# som.net
KiCad netlist of a schematic drawn in Altium Designer
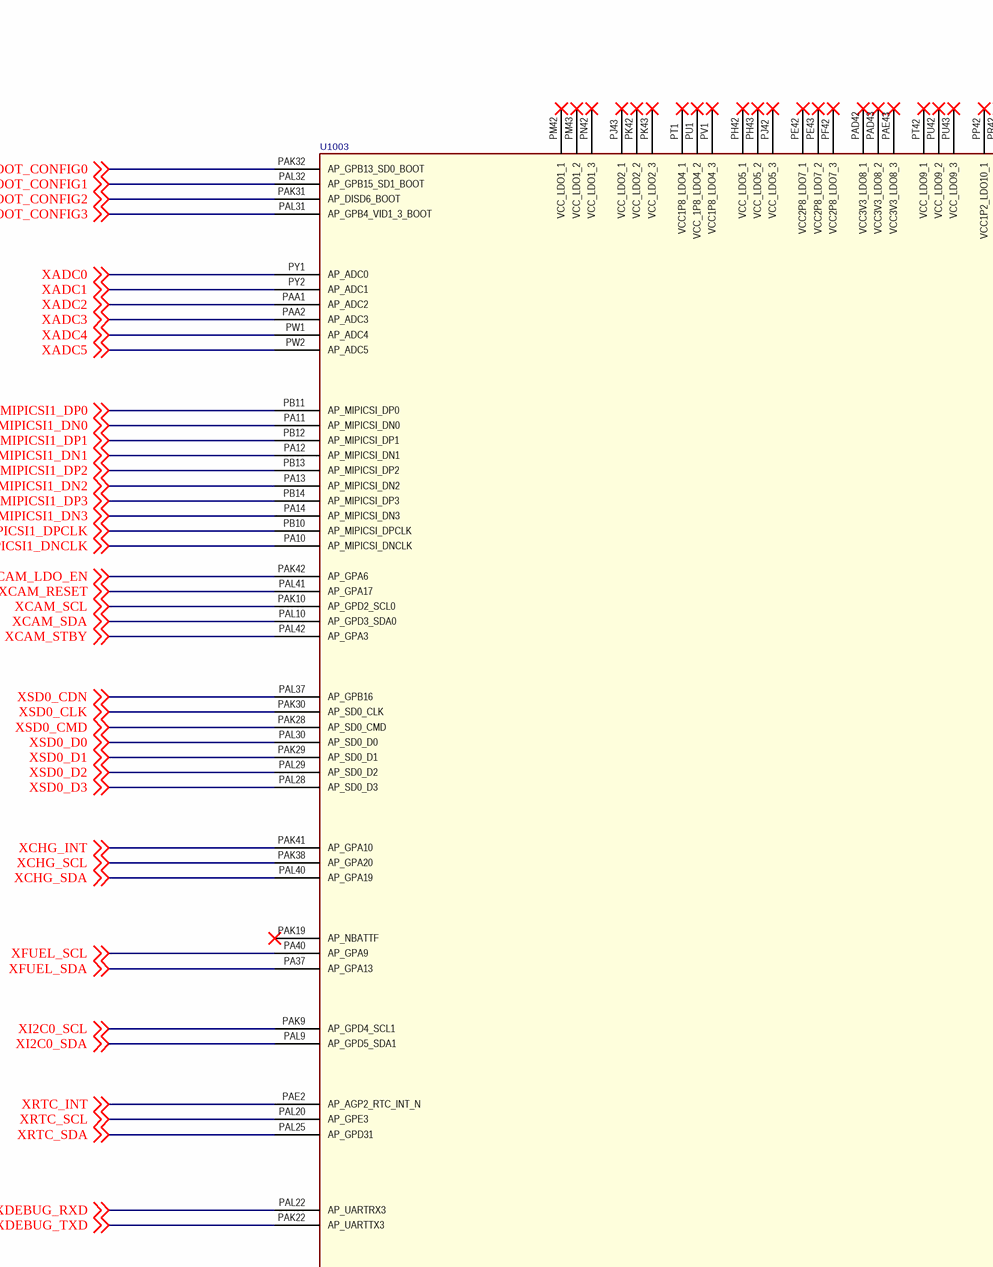
[diagram p0: som.SchDoc, top left]
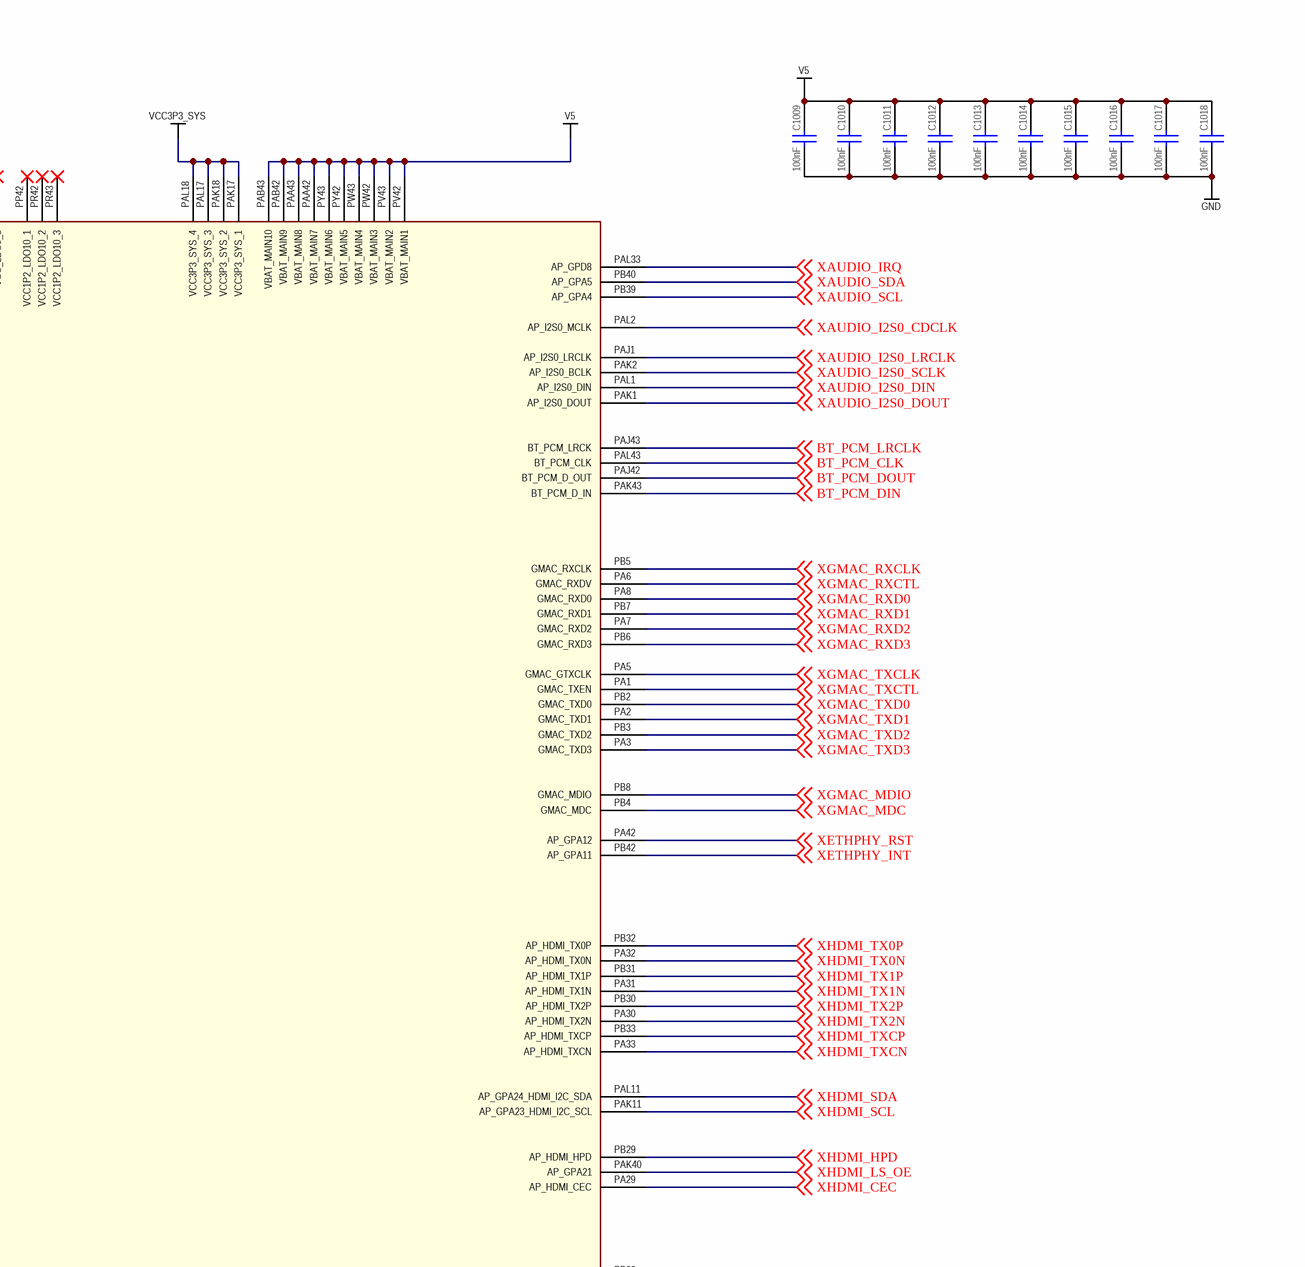
[diagram p1: som.SchDoc, top right]
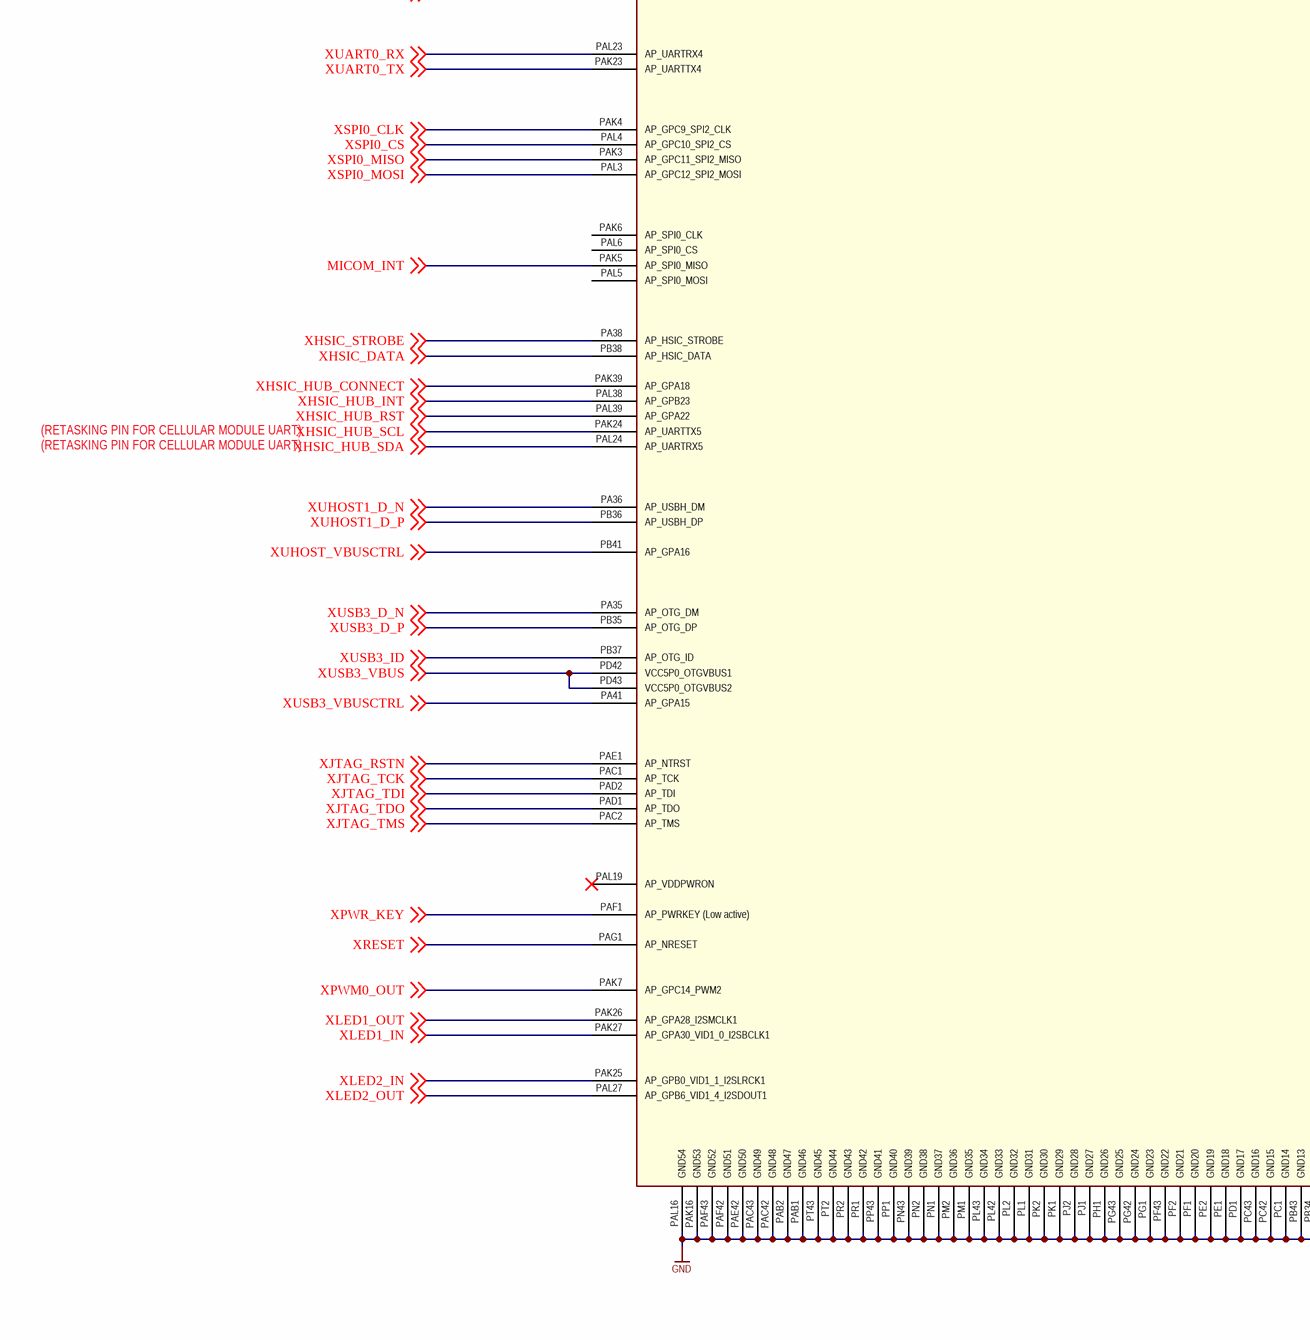
[diagram p2: som.SchDoc, bottom left]
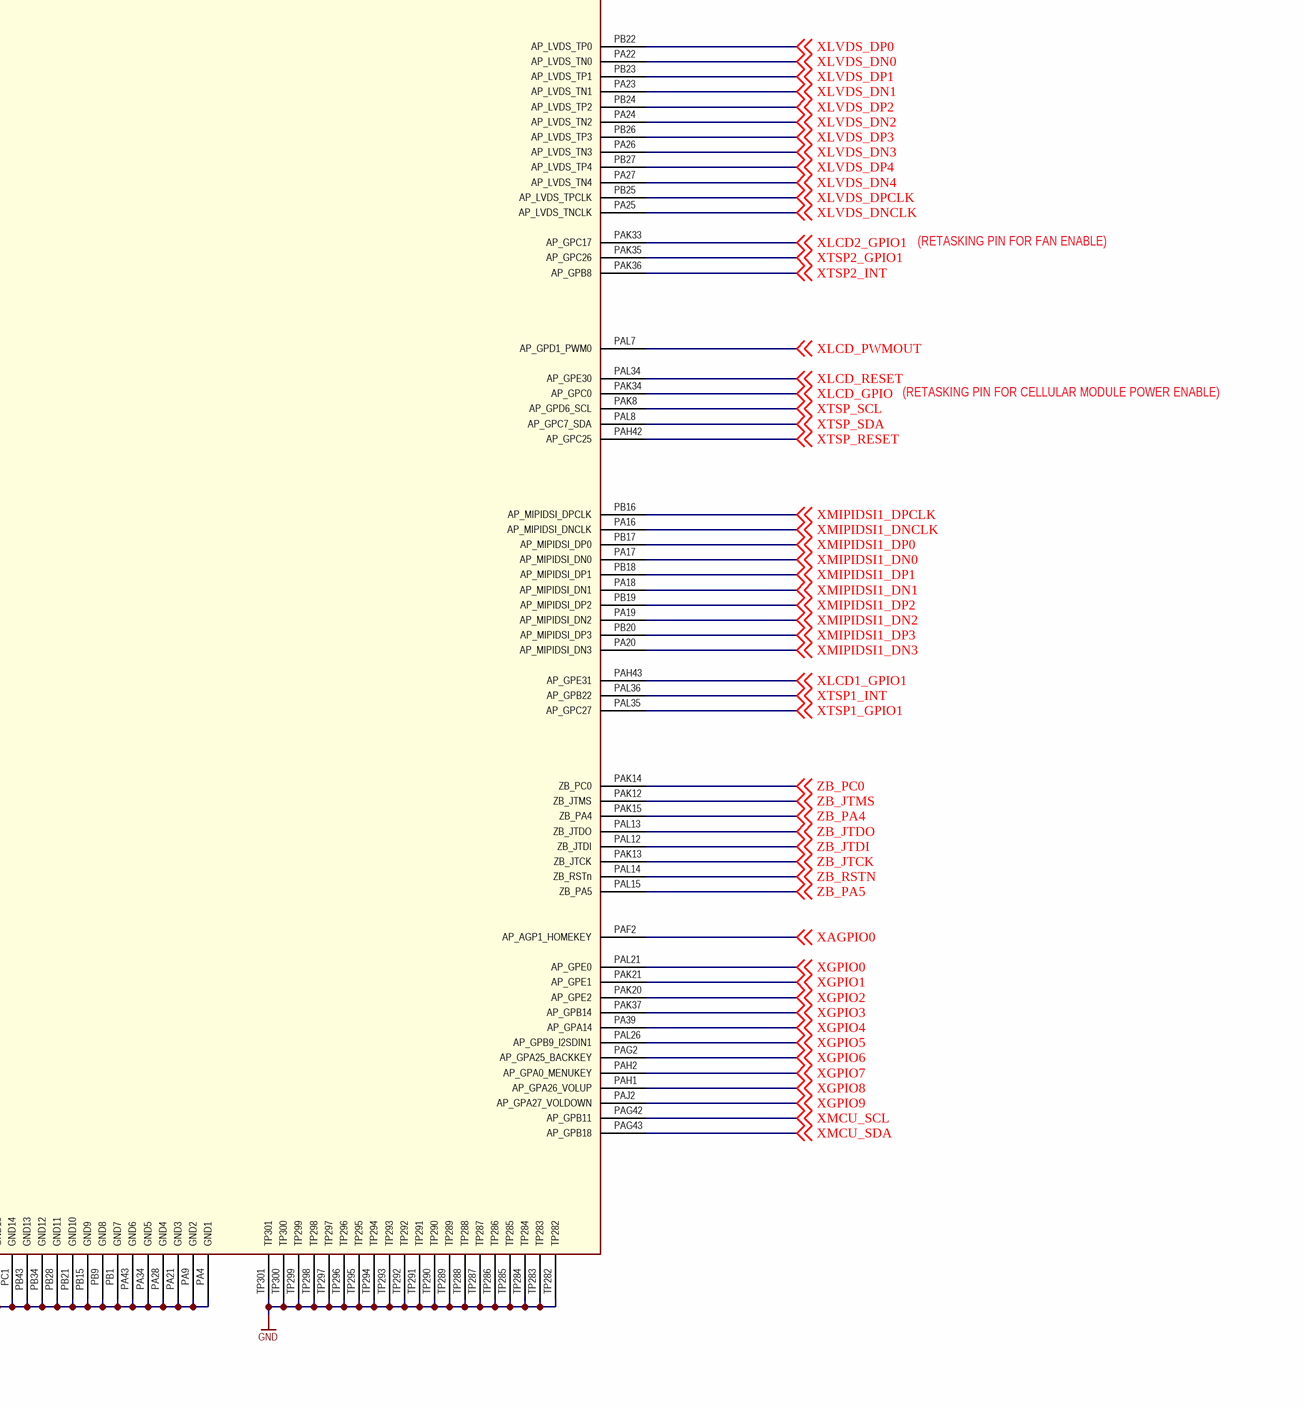
[diagram p3: som.SchDoc, bottom right]

(export (version "E")
  (design (tool "Eeschema 10.0.6"))
  (components
    (comp (ref "C1009")
      (value "100nF")
      (footprint "CAPC100X50X55L25N")
      (description "Ceramic Capacitor 100nF ±10% 50V X7R 0402")
      (fields (field (name "MANUFACTURER") "Murata") (field (name "TOLERANCE") "±10%"))
      (libsource (lib "generic") (part "CAP"))
    )
    (comp (ref "C1010")
      (value "100nF")
      (footprint "CAPC100X50X55L25N")
      (description "Ceramic Capacitor 100nF ±10% 50V X7R 0402")
      (fields (field (name "MANUFACTURER") "Murata") (field (name "TOLERANCE") "±10%"))
      (libsource (lib "generic") (part "CAP"))
    )
    (comp (ref "C1011")
      (value "100nF")
      (footprint "CAPC100X50X55L25N")
      (description "Ceramic Capacitor 100nF ±10% 50V X7R 0402")
      (fields (field (name "MANUFACTURER") "Murata") (field (name "TOLERANCE") "±10%"))
      (libsource (lib "generic") (part "CAP"))
    )
    (comp (ref "C1012")
      (value "100nF")
      (footprint "CAPC100X50X55L25N")
      (description "Ceramic Capacitor 100nF ±10% 50V X7R 0402")
      (fields (field (name "MANUFACTURER") "Murata") (field (name "TOLERANCE") "±10%"))
      (libsource (lib "generic") (part "CAP"))
    )
    (comp (ref "C1013")
      (value "100nF")
      (footprint "CAPC100X50X55L25N")
      (description "Ceramic Capacitor 100nF ±10% 50V X7R 0402")
      (fields (field (name "MANUFACTURER") "Murata") (field (name "TOLERANCE") "±10%"))
      (libsource (lib "generic") (part "CAP"))
    )
    (comp (ref "C1014")
      (value "100nF")
      (footprint "CAPC100X50X55L25N")
      (description "Ceramic Capacitor 100nF ±10% 50V X7R 0402")
      (fields (field (name "MANUFACTURER") "Murata") (field (name "TOLERANCE") "±10%"))
      (libsource (lib "generic") (part "CAP"))
    )
    (comp (ref "C1015")
      (value "100nF")
      (footprint "CAPC100X50X55L25N")
      (description "Ceramic Capacitor 100nF ±10% 50V X7R 0402")
      (fields (field (name "MANUFACTURER") "Murata") (field (name "TOLERANCE") "±10%"))
      (libsource (lib "generic") (part "CAP"))
    )
    (comp (ref "C1016")
      (value "100nF")
      (footprint "CAPC100X50X55L25N")
      (description "Ceramic Capacitor 100nF ±10% 50V X7R 0402")
      (fields (field (name "MANUFACTURER") "Murata") (field (name "TOLERANCE") "±10%"))
      (libsource (lib "generic") (part "CAP"))
    )
    (comp (ref "C1017")
      (value "100nF")
      (footprint "CAPC100X50X55L25N")
      (description "Ceramic Capacitor 100nF ±10% 50V X7R 0402")
      (fields (field (name "MANUFACTURER") "Murata") (field (name "TOLERANCE") "±10%"))
      (libsource (lib "generic") (part "CAP"))
    )
    (comp (ref "C1018")
      (value "100nF")
      (footprint "CAPC100X50X55L25N")
      (description "Ceramic Capacitor 100nF ±10% 50V X7R 0402")
      (fields (field (name "MANUFACTURER") "Murata") (field (name "TOLERANCE") "±10%"))
      (libsource (lib "generic") (part "CAP"))
    )
    (comp (ref "U1003")
      (value "ARTIK_710_LGA_PAD")
      (footprint "samsung:ARTIK_LGA_PAD_10")
      (description "ARTIK 710 System on Module")
      (fields (field (name "MANUFACTURER") "Samsung"))
      (libsource (lib "*") (part "ARTIK_LGA_PAD_10"))
    )
  )
  (nets
    (net (code "1") (name "BT_PCM_CLK") (class "Default")
      (node (ref "U1003") (pin "PAL43") (pinfunction "BT_PCM_CLK_PAL43") (pintype "passive"))
    )
    (net (code "2") (name "BT_PCM_DIN") (class "Default")
      (node (ref "U1003") (pin "PAK43") (pinfunction "BT_PCM_D_IN_PAK43") (pintype "passive"))
    )
    (net (code "3") (name "BT_PCM_DOUT") (class "Default")
      (node (ref "U1003") (pin "PAJ42") (pinfunction "BT_PCM_D_OUT_PAJ42") (pintype "passive"))
    )
    (net (code "4") (name "BT_PCM_LRCLK") (class "Default")
      (node (ref "U1003") (pin "PAJ43") (pinfunction "BT_PCM_LRCK_PAJ43") (pintype "passive"))
    )
    (net (code "5") (name "GND") (class "Default")
      (node (ref "C1009") (pin "1") (pinfunction "1_1") (pintype "passive"))
      (node (ref "C1010") (pin "1") (pinfunction "1_1") (pintype "passive"))
      (node (ref "C1011") (pin "1") (pinfunction "1_1") (pintype "passive"))
      (node (ref "C1012") (pin "1") (pinfunction "1_1") (pintype "passive"))
      (node (ref "C1013") (pin "1") (pinfunction "1_1") (pintype "passive"))
      (node (ref "C1014") (pin "1") (pinfunction "1_1") (pintype "passive"))
      (node (ref "C1015") (pin "1") (pinfunction "1_1") (pintype "passive"))
      (node (ref "C1016") (pin "1") (pinfunction "1_1") (pintype "passive"))
      (node (ref "C1017") (pin "1") (pinfunction "1_1") (pintype "passive"))
      (node (ref "C1018") (pin "1") (pinfunction "1_1") (pintype "passive"))
      (node (ref "U1003") (pin "PA21") (pinfunction "GND3_PA21") (pintype "passive"))
      (node (ref "U1003") (pin "PA28") (pinfunction "GND4_PA28") (pintype "passive"))
      (node (ref "U1003") (pin "PA34") (pinfunction "GND5_PA34") (pintype "passive"))
      (node (ref "U1003") (pin "PA4") (pinfunction "GND1_PA4") (pintype "passive"))
      (node (ref "U1003") (pin "PA43") (pinfunction "GND6_PA43") (pintype "passive"))
      (node (ref "U1003") (pin "PA9") (pinfunction "GND2_PA9") (pintype "passive"))
      (node (ref "U1003") (pin "PAB1") (pinfunction "GND46_PAB1") (pintype "passive"))
      (node (ref "U1003") (pin "PAB2") (pinfunction "GND47_PAB2") (pintype "passive"))
      (node (ref "U1003") (pin "PAC42") (pinfunction "GND48_PAC42") (pintype "passive"))
      (node (ref "U1003") (pin "PAC43") (pinfunction "GND49_PAC43") (pintype "passive"))
      (node (ref "U1003") (pin "PAE42") (pinfunction "GND50_PAE42") (pintype "passive"))
      (node (ref "U1003") (pin "PAF42") (pinfunction "GND51_PAF42") (pintype "passive"))
      (node (ref "U1003") (pin "PAF43") (pinfunction "GND52_PAF43") (pintype "passive"))
      (node (ref "U1003") (pin "PAK16") (pinfunction "GND53_PAK16") (pintype "passive"))
      (node (ref "U1003") (pin "PAL16") (pinfunction "GND54_PAL16") (pintype "passive"))
      (node (ref "U1003") (pin "PB1") (pinfunction "GND7_PB1") (pintype "passive"))
      (node (ref "U1003") (pin "PB15") (pinfunction "GND9_PB15") (pintype "passive"))
      (node (ref "U1003") (pin "PB21") (pinfunction "GND10_PB21") (pintype "passive"))
      (node (ref "U1003") (pin "PB28") (pinfunction "GND11_PB28") (pintype "passive"))
      (node (ref "U1003") (pin "PB34") (pinfunction "GND12_PB34") (pintype "passive"))
      (node (ref "U1003") (pin "PB43") (pinfunction "GND13_PB43") (pintype "passive"))
      (node (ref "U1003") (pin "PB9") (pinfunction "GND8_PB9") (pintype "passive"))
      (node (ref "U1003") (pin "PC1") (pinfunction "GND14_PC1") (pintype "passive"))
      (node (ref "U1003") (pin "PC42") (pinfunction "GND15_PC42") (pintype "passive"))
      (node (ref "U1003") (pin "PC43") (pinfunction "GND16_PC43") (pintype "passive"))
      (node (ref "U1003") (pin "PD1") (pinfunction "GND17_PD1") (pintype "passive"))
      (node (ref "U1003") (pin "PE1") (pinfunction "GND18_PE1") (pintype "passive"))
      (node (ref "U1003") (pin "PE2") (pinfunction "GND19_PE2") (pintype "passive"))
      (node (ref "U1003") (pin "PF1") (pinfunction "GND20_PF1") (pintype "passive"))
      (node (ref "U1003") (pin "PF2") (pinfunction "GND21_PF2") (pintype "passive"))
      (node (ref "U1003") (pin "PF43") (pinfunction "GND22_PF43") (pintype "passive"))
      (node (ref "U1003") (pin "PG1") (pinfunction "GND23_PG1") (pintype "passive"))
      (node (ref "U1003") (pin "PG42") (pinfunction "GND24_PG42") (pintype "passive"))
      (node (ref "U1003") (pin "PG43") (pinfunction "GND25_PG43") (pintype "passive"))
      (node (ref "U1003") (pin "PH1") (pinfunction "GND26_PH1") (pintype "passive"))
      (node (ref "U1003") (pin "PJ1") (pinfunction "GND27_PJ1") (pintype "passive"))
      (node (ref "U1003") (pin "PJ2") (pinfunction "GND28_PJ2") (pintype "passive"))
      (node (ref "U1003") (pin "PK1") (pinfunction "GND29_PK1") (pintype "passive"))
      (node (ref "U1003") (pin "PK2") (pinfunction "GND30_PK2") (pintype "passive"))
      (node (ref "U1003") (pin "PL1") (pinfunction "GND31_PL1") (pintype "passive"))
      (node (ref "U1003") (pin "PL2") (pinfunction "GND32_PL2") (pintype "passive"))
      (node (ref "U1003") (pin "PL42") (pinfunction "GND33_PL42") (pintype "passive"))
      (node (ref "U1003") (pin "PL43") (pinfunction "GND34_PL43") (pintype "passive"))
      (node (ref "U1003") (pin "PM1") (pinfunction "GND35_PM1") (pintype "passive"))
      (node (ref "U1003") (pin "PM2") (pinfunction "GND36_PM2") (pintype "passive"))
      (node (ref "U1003") (pin "PN1") (pinfunction "GND37_PN1") (pintype "passive"))
      (node (ref "U1003") (pin "PN2") (pinfunction "GND38_PN2") (pintype "passive"))
      (node (ref "U1003") (pin "PN43") (pinfunction "GND39_PN43") (pintype "passive"))
      (node (ref "U1003") (pin "PP1") (pinfunction "GND40_PP1") (pintype "passive"))
      (node (ref "U1003") (pin "PP43") (pinfunction "GND41_PP43") (pintype "passive"))
      (node (ref "U1003") (pin "PR1") (pinfunction "GND42_PR1") (pintype "passive"))
      (node (ref "U1003") (pin "PR2") (pinfunction "GND43_PR2") (pintype "passive"))
      (node (ref "U1003") (pin "PT2") (pinfunction "GND44_PT2") (pintype "passive"))
      (node (ref "U1003") (pin "PT43") (pinfunction "GND45_PT43") (pintype "passive"))
      (node (ref "U1003") (pin "TP282") (pinfunction "TP282_TP282") (pintype "passive"))
      (node (ref "U1003") (pin "TP283") (pinfunction "TP283_TP283") (pintype "passive"))
      (node (ref "U1003") (pin "TP284") (pinfunction "TP284_TP284") (pintype "passive"))
      (node (ref "U1003") (pin "TP285") (pinfunction "TP285_TP285") (pintype "passive"))
      (node (ref "U1003") (pin "TP286") (pinfunction "TP286_TP286") (pintype "passive"))
      (node (ref "U1003") (pin "TP287") (pinfunction "TP287_TP287") (pintype "passive"))
      (node (ref "U1003") (pin "TP288") (pinfunction "TP288_TP288") (pintype "passive"))
      (node (ref "U1003") (pin "TP289") (pinfunction "TP289_TP289") (pintype "passive"))
      (node (ref "U1003") (pin "TP290") (pinfunction "TP290_TP290") (pintype "passive"))
      (node (ref "U1003") (pin "TP291") (pinfunction "TP291_TP291") (pintype "passive"))
      (node (ref "U1003") (pin "TP292") (pinfunction "TP292_TP292") (pintype "passive"))
      (node (ref "U1003") (pin "TP293") (pinfunction "TP293_TP293") (pintype "passive"))
      (node (ref "U1003") (pin "TP294") (pinfunction "TP294_TP294") (pintype "passive"))
      (node (ref "U1003") (pin "TP295") (pinfunction "TP295_TP295") (pintype "passive"))
      (node (ref "U1003") (pin "TP296") (pinfunction "TP296_TP296") (pintype "passive"))
      (node (ref "U1003") (pin "TP297") (pinfunction "TP297_TP297") (pintype "passive"))
      (node (ref "U1003") (pin "TP298") (pinfunction "TP298_TP298") (pintype "passive"))
      (node (ref "U1003") (pin "TP299") (pinfunction "TP299_TP299") (pintype "passive"))
      (node (ref "U1003") (pin "TP300") (pinfunction "TP300_TP300") (pintype "passive"))
      (node (ref "U1003") (pin "TP301") (pinfunction "TP301_TP301") (pintype "passive"))
    )
    (net (code "6") (name "MICOM_INT") (class "Default")
      (node (ref "U1003") (pin "PAK5") (pinfunction "AP_SPI0_MISO_PAK5") (pintype "passive"))
    )
    (net (code "7") (name "V5") (class "Default")
      (node (ref "C1009") (pin "2") (pinfunction "2_2") (pintype "passive"))
      (node (ref "C1010") (pin "2") (pinfunction "2_2") (pintype "passive"))
      (node (ref "C1011") (pin "2") (pinfunction "2_2") (pintype "passive"))
      (node (ref "C1012") (pin "2") (pinfunction "2_2") (pintype "passive"))
      (node (ref "C1013") (pin "2") (pinfunction "2_2") (pintype "passive"))
      (node (ref "C1014") (pin "2") (pinfunction "2_2") (pintype "passive"))
      (node (ref "C1015") (pin "2") (pinfunction "2_2") (pintype "passive"))
      (node (ref "C1016") (pin "2") (pinfunction "2_2") (pintype "passive"))
      (node (ref "C1017") (pin "2") (pinfunction "2_2") (pintype "passive"))
      (node (ref "C1018") (pin "2") (pinfunction "2_2") (pintype "passive"))
      (node (ref "U1003") (pin "PAA42") (pinfunction "VBAT_MAIN7_PAA42") (pintype "passive"))
      (node (ref "U1003") (pin "PAA43") (pinfunction "VBAT_MAIN8_PAA43") (pintype "passive"))
      (node (ref "U1003") (pin "PAB42") (pinfunction "VBAT_MAIN9_PAB42") (pintype "passive"))
      (node (ref "U1003") (pin "PAB43") (pinfunction "VBAT_MAIN10_PAB43") (pintype "passive"))
      (node (ref "U1003") (pin "PV42") (pinfunction "VBAT_MAIN1_PV42") (pintype "passive"))
      (node (ref "U1003") (pin "PV43") (pinfunction "VBAT_MAIN2_PV43") (pintype "passive"))
      (node (ref "U1003") (pin "PW42") (pinfunction "VBAT_MAIN3_PW42") (pintype "passive"))
      (node (ref "U1003") (pin "PW43") (pinfunction "VBAT_MAIN4_PW43") (pintype "passive"))
      (node (ref "U1003") (pin "PY42") (pinfunction "VBAT_MAIN5_PY42") (pintype "passive"))
      (node (ref "U1003") (pin "PY43") (pinfunction "VBAT_MAIN6_PY43") (pintype "passive"))
    )
    (net (code "8") (name "VCC3P3_SYS") (class "Default")
      (node (ref "U1003") (pin "PAK17") (pinfunction "VCC3P3_SYS_1_PAK17") (pintype "passive"))
      (node (ref "U1003") (pin "PAK18") (pinfunction "VCC3P3_SYS_2_PAK18") (pintype "passive"))
      (node (ref "U1003") (pin "PAL17") (pinfunction "VCC3P3_SYS_3_PAL17") (pintype "passive"))
      (node (ref "U1003") (pin "PAL18") (pinfunction "VCC3P3_SYS_4_PAL18") (pintype "passive"))
    )
    (net (code "9") (name "XADC0") (class "Default")
      (node (ref "U1003") (pin "PY1") (pinfunction "AP_ADC0_PY1") (pintype "passive"))
    )
    (net (code "10") (name "XADC1") (class "Default")
      (node (ref "U1003") (pin "PY2") (pinfunction "AP_ADC1_PY2") (pintype "passive"))
    )
    (net (code "11") (name "XADC2") (class "Default")
      (node (ref "U1003") (pin "PAA1") (pinfunction "AP_ADC2_PAA1") (pintype "passive"))
    )
    (net (code "12") (name "XADC3") (class "Default")
      (node (ref "U1003") (pin "PAA2") (pinfunction "AP_ADC3_PAA2") (pintype "passive"))
    )
    (net (code "13") (name "XADC4") (class "Default")
      (node (ref "U1003") (pin "PW1") (pinfunction "AP_ADC4_PW1") (pintype "passive"))
    )
    (net (code "14") (name "XADC5") (class "Default")
      (node (ref "U1003") (pin "PW2") (pinfunction "AP_ADC5_PW2") (pintype "passive"))
    )
    (net (code "15") (name "XAGPIO0") (class "Default")
      (node (ref "U1003") (pin "PAF2") (pinfunction "AP_AGP1_HOMEKEY_PAF2") (pintype "passive"))
    )
    (net (code "16") (name "XAUDIO_I2S0_CDCLK") (class "Default")
      (node (ref "U1003") (pin "PAL2") (pinfunction "AP_I2S0_MCLK_PAL2") (pintype "passive"))
    )
    (net (code "17") (name "XAUDIO_I2S0_DIN") (class "Default")
      (node (ref "U1003") (pin "PAL1") (pinfunction "AP_I2S0_DIN_PAL1") (pintype "passive"))
    )
    (net (code "18") (name "XAUDIO_I2S0_DOUT") (class "Default")
      (node (ref "U1003") (pin "PAK1") (pinfunction "AP_I2S0_DOUT_PAK1") (pintype "passive"))
    )
    (net (code "19") (name "XAUDIO_I2S0_LRCLK") (class "Default")
      (node (ref "U1003") (pin "PAJ1") (pinfunction "AP_I2S0_LRCLK_PAJ1") (pintype "passive"))
    )
    (net (code "20") (name "XAUDIO_I2S0_SCLK") (class "Default")
      (node (ref "U1003") (pin "PAK2") (pinfunction "AP_I2S0_BCLK_PAK2") (pintype "passive"))
    )
    (net (code "21") (name "XAUDIO_IRQ") (class "Default")
      (node (ref "U1003") (pin "PAL33") (pinfunction "AP_GPD8_PAL33") (pintype "passive"))
    )
    (net (code "22") (name "XAUDIO_SCL") (class "Default")
      (node (ref "U1003") (pin "PB39") (pinfunction "AP_GPA4_PB39") (pintype "passive"))
    )
    (net (code "23") (name "XAUDIO_SDA") (class "Default")
      (node (ref "U1003") (pin "PB40") (pinfunction "AP_GPA5_PB40") (pintype "passive"))
    )
    (net (code "24") (name "XBOOT_CONFIG0") (class "Default")
      (node (ref "U1003") (pin "PAK32") (pinfunction "AP_GPB13_SD0_BOOT_PAK32") (pintype "passive"))
    )
    (net (code "25") (name "XBOOT_CONFIG1") (class "Default")
      (node (ref "U1003") (pin "PAL32") (pinfunction "AP_GPB15_SD1_BOOT_PAL32") (pintype "passive"))
    )
    (net (code "26") (name "XBOOT_CONFIG2") (class "Default")
      (node (ref "U1003") (pin "PAK31") (pinfunction "AP_DISD6_BOOT_PAK31") (pintype "passive"))
    )
    (net (code "27") (name "XBOOT_CONFIG3") (class "Default")
      (node (ref "U1003") (pin "PAL31") (pinfunction "AP_GPB4_VID1_3_BOOT_PAL31") (pintype "passive"))
    )
    (net (code "28") (name "XCAM_LDO_EN") (class "Default")
      (node (ref "U1003") (pin "PAK42") (pinfunction "AP_GPA6_PAK42") (pintype "passive"))
    )
    (net (code "29") (name "XCAM_RESET") (class "Default")
      (node (ref "U1003") (pin "PAL41") (pinfunction "AP_GPA17_PAL41") (pintype "passive"))
    )
    (net (code "30") (name "XCAM_SCL") (class "Default")
      (node (ref "U1003") (pin "PAK10") (pinfunction "AP_GPD2_SCL0_PAK10") (pintype "passive"))
    )
    (net (code "31") (name "XCAM_SDA") (class "Default")
      (node (ref "U1003") (pin "PAL10") (pinfunction "AP_GPD3_SDA0_PAL10") (pintype "passive"))
    )
    (net (code "32") (name "XCAM_STBY") (class "Default")
      (node (ref "U1003") (pin "PAL42") (pinfunction "AP_GPA3_PAL42") (pintype "passive"))
    )
    (net (code "33") (name "XCHG_INT") (class "Default")
      (node (ref "U1003") (pin "PAK41") (pinfunction "AP_GPA10_PAK41") (pintype "passive"))
    )
    (net (code "34") (name "XCHG_SCL") (class "Default")
      (node (ref "U1003") (pin "PAK38") (pinfunction "AP_GPA20_PAK38") (pintype "passive"))
    )
    (net (code "35") (name "XCHG_SDA") (class "Default")
      (node (ref "U1003") (pin "PAL40") (pinfunction "AP_GPA19_PAL40") (pintype "passive"))
    )
    (net (code "36") (name "XDEBUG_RXD") (class "Default")
      (node (ref "U1003") (pin "PAL22") (pinfunction "AP_UARTRX3_PAL22") (pintype "passive"))
    )
    (net (code "37") (name "XDEBUG_TXD") (class "Default")
      (node (ref "U1003") (pin "PAK22") (pinfunction "AP_UARTTX3_PAK22") (pintype "passive"))
    )
    (net (code "38") (name "XETHPHY_INT") (class "Default")
      (node (ref "U1003") (pin "PB42") (pinfunction "AP_GPA11_PB42") (pintype "passive"))
    )
    (net (code "39") (name "XETHPHY_RST") (class "Default")
      (node (ref "U1003") (pin "PA42") (pinfunction "AP_GPA12_PA42") (pintype "passive"))
    )
    (net (code "40") (name "XFUEL_SCL") (class "Default")
      (node (ref "U1003") (pin "PA40") (pinfunction "AP_GPA9_PA40") (pintype "passive"))
    )
    (net (code "41") (name "XFUEL_SDA") (class "Default")
      (node (ref "U1003") (pin "PA37") (pinfunction "AP_GPA13_PA37") (pintype "passive"))
    )
    (net (code "42") (name "XGMAC_MDC") (class "Default")
      (node (ref "U1003") (pin "PB4") (pinfunction "GMAC_MDC_PB4") (pintype "passive"))
    )
    (net (code "43") (name "XGMAC_MDIO") (class "Default")
      (node (ref "U1003") (pin "PB8") (pinfunction "GMAC_MDIO_PB8") (pintype "passive"))
    )
    (net (code "44") (name "XGMAC_RXCLK") (class "Default")
      (node (ref "U1003") (pin "PB5") (pinfunction "GMAC_RXCLK_PB5") (pintype "passive"))
    )
    (net (code "45") (name "XGMAC_RXCTL") (class "Default")
      (node (ref "U1003") (pin "PA6") (pinfunction "GMAC_RXDV_PA6") (pintype "passive"))
    )
    (net (code "46") (name "XGMAC_RXD0") (class "Default")
      (node (ref "U1003") (pin "PA8") (pinfunction "GMAC_RXD0_PA8") (pintype "passive"))
    )
    (net (code "47") (name "XGMAC_RXD1") (class "Default")
      (node (ref "U1003") (pin "PB7") (pinfunction "GMAC_RXD1_PB7") (pintype "passive"))
    )
    (net (code "48") (name "XGMAC_RXD2") (class "Default")
      (node (ref "U1003") (pin "PA7") (pinfunction "GMAC_RXD2_PA7") (pintype "passive"))
    )
    (net (code "49") (name "XGMAC_RXD3") (class "Default")
      (node (ref "U1003") (pin "PB6") (pinfunction "GMAC_RXD3_PB6") (pintype "passive"))
    )
    (net (code "50") (name "XGMAC_TXCLK") (class "Default")
      (node (ref "U1003") (pin "PA5") (pinfunction "GMAC_GTXCLK_PA5") (pintype "passive"))
    )
    (net (code "51") (name "XGMAC_TXCTL") (class "Default")
      (node (ref "U1003") (pin "PA1") (pinfunction "GMAC_TXEN_PA1") (pintype "passive"))
    )
    (net (code "52") (name "XGMAC_TXD0") (class "Default")
      (node (ref "U1003") (pin "PB2") (pinfunction "GMAC_TXD0_PB2") (pintype "passive"))
    )
    (net (code "53") (name "XGMAC_TXD1") (class "Default")
      (node (ref "U1003") (pin "PA2") (pinfunction "GMAC_TXD1_PA2") (pintype "passive"))
    )
    (net (code "54") (name "XGMAC_TXD2") (class "Default")
      (node (ref "U1003") (pin "PB3") (pinfunction "GMAC_TXD2_PB3") (pintype "passive"))
    )
    (net (code "55") (name "XGMAC_TXD3") (class "Default")
      (node (ref "U1003") (pin "PA3") (pinfunction "GMAC_TXD3_PA3") (pintype "passive"))
    )
    (net (code "56") (name "XGPIO0") (class "Default")
      (node (ref "U1003") (pin "PAL21") (pinfunction "AP_GPE0_PAL21") (pintype "passive"))
    )
    (net (code "57") (name "XGPIO1") (class "Default")
      (node (ref "U1003") (pin "PAK21") (pinfunction "AP_GPE1_PAK21") (pintype "passive"))
    )
    (net (code "58") (name "XGPIO2") (class "Default")
      (node (ref "U1003") (pin "PAK20") (pinfunction "AP_GPE2_PAK20") (pintype "passive"))
    )
    (net (code "59") (name "XGPIO3") (class "Default")
      (node (ref "U1003") (pin "PAK37") (pinfunction "AP_GPB14_PAK37") (pintype "passive"))
    )
    (net (code "60") (name "XGPIO4") (class "Default")
      (node (ref "U1003") (pin "PA39") (pinfunction "AP_GPA14_PA39") (pintype "passive"))
    )
    (net (code "61") (name "XGPIO5") (class "Default")
      (node (ref "U1003") (pin "PAL26") (pinfunction "AP_GPB9_I2SDIN1_PAL26") (pintype "passive"))
    )
    (net (code "62") (name "XGPIO6") (class "Default")
      (node (ref "U1003") (pin "PAG2") (pinfunction "AP_GPA25_BACKKEY_PAG2") (pintype "passive"))
    )
    (net (code "63") (name "XGPIO7") (class "Default")
      (node (ref "U1003") (pin "PAH2") (pinfunction "AP_GPA0_MENUKEY_PAH2") (pintype "passive"))
    )
    (net (code "64") (name "XGPIO8") (class "Default")
      (node (ref "U1003") (pin "PAH1") (pinfunction "AP_GPA26_VOLUP_PAH1") (pintype "passive"))
    )
    (net (code "65") (name "XGPIO9") (class "Default")
      (node (ref "U1003") (pin "PAJ2") (pinfunction "AP_GPA27_VOLDOWN_PAJ2") (pintype "passive"))
    )
    (net (code "66") (name "XHDMI_CEC") (class "Default")
      (node (ref "U1003") (pin "PA29") (pinfunction "AP_HDMI_CEC_PA29") (pintype "passive"))
    )
    (net (code "67") (name "XHDMI_HPD") (class "Default")
      (node (ref "U1003") (pin "PB29") (pinfunction "AP_HDMI_HPD_PB29") (pintype "passive"))
    )
    (net (code "68") (name "XHDMI_LS_OE") (class "Default")
      (node (ref "U1003") (pin "PAK40") (pinfunction "AP_GPA21_PAK40") (pintype "passive"))
    )
    (net (code "69") (name "XHDMI_SCL") (class "Default")
      (node (ref "U1003") (pin "PAK11") (pinfunction "AP_GPA23_HDMI_I2C_SCL_PAK11") (pintype "passive"))
    )
    (net (code "70") (name "XHDMI_SDA") (class "Default")
      (node (ref "U1003") (pin "PAL11") (pinfunction "AP_GPA24_HDMI_I2C_SDA_PAL11") (pintype "passive"))
    )
    (net (code "71") (name "XHDMI_TX0N") (class "Default")
      (node (ref "U1003") (pin "PA32") (pinfunction "AP_HDMI_TX0N_PA32") (pintype "passive"))
    )
    (net (code "72") (name "XHDMI_TX0P") (class "Default")
      (node (ref "U1003") (pin "PB32") (pinfunction "AP_HDMI_TX0P_PB32") (pintype "passive"))
    )
    (net (code "73") (name "XHDMI_TX1N") (class "Default")
      (node (ref "U1003") (pin "PA31") (pinfunction "AP_HDMI_TX1N_PA31") (pintype "passive"))
    )
    (net (code "74") (name "XHDMI_TX1P") (class "Default")
      (node (ref "U1003") (pin "PB31") (pinfunction "AP_HDMI_TX1P_PB31") (pintype "passive"))
    )
    (net (code "75") (name "XHDMI_TX2N") (class "Default")
      (node (ref "U1003") (pin "PA30") (pinfunction "AP_HDMI_TX2N_PA30") (pintype "passive"))
    )
    (net (code "76") (name "XHDMI_TX2P") (class "Default")
      (node (ref "U1003") (pin "PB30") (pinfunction "AP_HDMI_TX2P_PB30") (pintype "passive"))
    )
    (net (code "77") (name "XHDMI_TXCN") (class "Default")
      (node (ref "U1003") (pin "PA33") (pinfunction "AP_HDMI_TXCN_PA33") (pintype "passive"))
    )
    (net (code "78") (name "XHDMI_TXCP") (class "Default")
      (node (ref "U1003") (pin "PB33") (pinfunction "AP_HDMI_TXCP_PB33") (pintype "passive"))
    )
    (net (code "79") (name "XHSIC_DATA") (class "Default")
      (node (ref "U1003") (pin "PB38") (pinfunction "AP_HSIC_DATA_PB38") (pintype "passive"))
    )
    (net (code "80") (name "XHSIC_HUB_CONNECT") (class "Default")
      (node (ref "U1003") (pin "PAK39") (pinfunction "AP_GPA18_PAK39") (pintype "passive"))
    )
    (net (code "81") (name "XHSIC_HUB_INT") (class "Default")
      (node (ref "U1003") (pin "PAL38") (pinfunction "AP_GPB23_PAL38") (pintype "passive"))
    )
    (net (code "82") (name "XHSIC_HUB_RST") (class "Default")
      (node (ref "U1003") (pin "PAL39") (pinfunction "AP_GPA22_PAL39") (pintype "passive"))
    )
    (net (code "83") (name "XHSIC_HUB_SCL") (class "Default")
      (node (ref "U1003") (pin "PAK24") (pinfunction "AP_UARTTX5_PAK24") (pintype "passive"))
    )
    (net (code "84") (name "XHSIC_HUB_SDA") (class "Default")
      (node (ref "U1003") (pin "PAL24") (pinfunction "AP_UARTRX5_PAL24") (pintype "passive"))
    )
    (net (code "85") (name "XHSIC_STROBE") (class "Default")
      (node (ref "U1003") (pin "PA38") (pinfunction "AP_HSIC_STROBE_PA38") (pintype "passive"))
    )
    (net (code "86") (name "XI2C0_SCL") (class "Default")
      (node (ref "U1003") (pin "PAK9") (pinfunction "AP_GPD4_SCL1_PAK9") (pintype "passive"))
    )
    (net (code "87") (name "XI2C0_SDA") (class "Default")
      (node (ref "U1003") (pin "PAL9") (pinfunction "AP_GPD5_SDA1_PAL9") (pintype "passive"))
    )
    (net (code "88") (name "XJTAG_RSTN") (class "Default")
      (node (ref "U1003") (pin "PAE1") (pinfunction "AP_NTRST_PAE1") (pintype "passive"))
    )
    (net (code "89") (name "XJTAG_TCK") (class "Default")
      (node (ref "U1003") (pin "PAC1") (pinfunction "AP_TCK_PAC1") (pintype "passive"))
    )
    (net (code "90") (name "XJTAG_TDI") (class "Default")
      (node (ref "U1003") (pin "PAD2") (pinfunction "AP_TDI_PAD2") (pintype "passive"))
    )
    (net (code "91") (name "XJTAG_TDO") (class "Default")
      (node (ref "U1003") (pin "PAD1") (pinfunction "AP_TDO_PAD1") (pintype "passive"))
    )
    (net (code "92") (name "XJTAG_TMS") (class "Default")
      (node (ref "U1003") (pin "PAC2") (pinfunction "AP_TMS_PAC2") (pintype "passive"))
    )
    (net (code "93") (name "XLCD1_GPIO1") (class "Default")
      (node (ref "U1003") (pin "PAH43") (pinfunction "AP_GPE31_PAH43") (pintype "passive"))
    )
    (net (code "94") (name "XLCD2_GPIO1") (class "Default")
      (node (ref "U1003") (pin "PAK33") (pinfunction "AP_GPC17_PAK33") (pintype "passive"))
    )
    (net (code "95") (name "XLCD_GPIO") (class "Default")
      (node (ref "U1003") (pin "PAK34") (pinfunction "AP_GPC0_PAK34") (pintype "passive"))
    )
    (net (code "96") (name "XLCD_PWMOUT") (class "Default")
      (node (ref "U1003") (pin "PAL7") (pinfunction "AP_GPD1_PWM0_PAL7") (pintype "passive"))
    )
    (net (code "97") (name "XLCD_RESET") (class "Default")
      (node (ref "U1003") (pin "PAL34") (pinfunction "AP_GPE30_PAL34") (pintype "passive"))
    )
    (net (code "98") (name "XLED1_IN") (class "Default")
      (node (ref "U1003") (pin "PAK27") (pinfunction "AP_GPA30_VID1_0_I2SBCLK1_PAK27") (pintype "passive"))
    )
    (net (code "99") (name "XLED1_OUT") (class "Default")
      (node (ref "U1003") (pin "PAK26") (pinfunction "AP_GPA28_I2SMCLK1_PAK26") (pintype "passive"))
    )
    (net (code "100") (name "XLED2_IN") (class "Default")
      (node (ref "U1003") (pin "PAK25") (pinfunction "AP_GPB0_VID1_1_I2SLRCK1_PAK25") (pintype "passive"))
    )
    (net (code "101") (name "XLED2_OUT") (class "Default")
      (node (ref "U1003") (pin "PAL27") (pinfunction "AP_GPB6_VID1_4_I2SDOUT1_PAL27") (pintype "passive"))
    )
    (net (code "102") (name "XLVDS_DN0") (class "Default")
      (node (ref "U1003") (pin "PA22") (pinfunction "AP_LVDS_TN0_PA22") (pintype "passive"))
    )
    (net (code "103") (name "XLVDS_DN1") (class "Default")
      (node (ref "U1003") (pin "PA23") (pinfunction "AP_LVDS_TN1_PA23") (pintype "passive"))
    )
    (net (code "104") (name "XLVDS_DN2") (class "Default")
      (node (ref "U1003") (pin "PA24") (pinfunction "AP_LVDS_TN2_PA24") (pintype "passive"))
    )
    (net (code "105") (name "XLVDS_DN3") (class "Default")
      (node (ref "U1003") (pin "PA26") (pinfunction "AP_LVDS_TN3_PA26") (pintype "passive"))
    )
    (net (code "106") (name "XLVDS_DN4") (class "Default")
      (node (ref "U1003") (pin "PA27") (pinfunction "AP_LVDS_TN4_PA27") (pintype "passive"))
    )
    (net (code "107") (name "XLVDS_DNCLK") (class "Default")
      (node (ref "U1003") (pin "PA25") (pinfunction "AP_LVDS_TNCLK_PA25") (pintype "passive"))
    )
    (net (code "108") (name "XLVDS_DP0") (class "Default")
      (node (ref "U1003") (pin "PB22") (pinfunction "AP_LVDS_TP0_PB22") (pintype "passive"))
    )
    (net (code "109") (name "XLVDS_DP1") (class "Default")
      (node (ref "U1003") (pin "PB23") (pinfunction "AP_LVDS_TP1_PB23") (pintype "passive"))
    )
    (net (code "110") (name "XLVDS_DP2") (class "Default")
      (node (ref "U1003") (pin "PB24") (pinfunction "AP_LVDS_TP2_PB24") (pintype "passive"))
    )
    (net (code "111") (name "XLVDS_DP3") (class "Default")
      (node (ref "U1003") (pin "PB26") (pinfunction "AP_LVDS_TP3_PB26") (pintype "passive"))
    )
    (net (code "112") (name "XLVDS_DP4") (class "Default")
      (node (ref "U1003") (pin "PB27") (pinfunction "AP_LVDS_TP4_PB27") (pintype "passive"))
    )
    (net (code "113") (name "XLVDS_DPCLK") (class "Default")
      (node (ref "U1003") (pin "PB25") (pinfunction "AP_LVDS_TPCLK_PB25") (pintype "passive"))
    )
    (net (code "114") (name "XMCU_SCL") (class "Default")
      (node (ref "U1003") (pin "PAG42") (pinfunction "AP_GPB11_PAG42") (pintype "passive"))
    )
    (net (code "115") (name "XMCU_SDA") (class "Default")
      (node (ref "U1003") (pin "PAG43") (pinfunction "AP_GPB18_PAG43") (pintype "passive"))
    )
    (net (code "116") (name "XMIPICSI1_DN0") (class "Default")
      (node (ref "U1003") (pin "PA11") (pinfunction "AP_MIPICSI_DN0_PA11") (pintype "passive"))
    )
    (net (code "117") (name "XMIPICSI1_DN1") (class "Default")
      (node (ref "U1003") (pin "PA12") (pinfunction "AP_MIPICSI_DN1_PA12") (pintype "passive"))
    )
    (net (code "118") (name "XMIPICSI1_DN2") (class "Default")
      (node (ref "U1003") (pin "PA13") (pinfunction "AP_MIPICSI_DN2_PA13") (pintype "passive"))
    )
    (net (code "119") (name "XMIPICSI1_DN3") (class "Default")
      (node (ref "U1003") (pin "PA14") (pinfunction "AP_MIPICSI_DN3_PA14") (pintype "passive"))
    )
    (net (code "120") (name "XMIPICSI1_DNCLK") (class "Default")
      (node (ref "U1003") (pin "PA10") (pinfunction "AP_MIPICSI_DNCLK_PA10") (pintype "passive"))
    )
    (net (code "121") (name "XMIPICSI1_DP0") (class "Default")
      (node (ref "U1003") (pin "PB11") (pinfunction "AP_MIPICSI_DP0_PB11") (pintype "passive"))
    )
    (net (code "122") (name "XMIPICSI1_DP1") (class "Default")
      (node (ref "U1003") (pin "PB12") (pinfunction "AP_MIPICSI_DP1_PB12") (pintype "passive"))
    )
    (net (code "123") (name "XMIPICSI1_DP2") (class "Default")
      (node (ref "U1003") (pin "PB13") (pinfunction "AP_MIPICSI_DP2_PB13") (pintype "passive"))
    )
    (net (code "124") (name "XMIPICSI1_DP3") (class "Default")
      (node (ref "U1003") (pin "PB14") (pinfunction "AP_MIPICSI_DP3_PB14") (pintype "passive"))
    )
    (net (code "125") (name "XMIPICSI1_DPCLK") (class "Default")
      (node (ref "U1003") (pin "PB10") (pinfunction "AP_MIPICSI_DPCLK_PB10") (pintype "passive"))
    )
    (net (code "126") (name "XMIPIDSI1_DN0") (class "Default")
      (node (ref "U1003") (pin "PA17") (pinfunction "AP_MIPIDSI_DN0_PA17") (pintype "passive"))
    )
    (net (code "127") (name "XMIPIDSI1_DN1") (class "Default")
      (node (ref "U1003") (pin "PA18") (pinfunction "AP_MIPIDSI_DN1_PA18") (pintype "passive"))
    )
    (net (code "128") (name "XMIPIDSI1_DN2") (class "Default")
      (node (ref "U1003") (pin "PA19") (pinfunction "AP_MIPIDSI_DN2_PA19") (pintype "passive"))
    )
    (net (code "129") (name "XMIPIDSI1_DN3") (class "Default")
      (node (ref "U1003") (pin "PA20") (pinfunction "AP_MIPIDSI_DN3_PA20") (pintype "passive"))
    )
    (net (code "130") (name "XMIPIDSI1_DNCLK") (class "Default")
      (node (ref "U1003") (pin "PA16") (pinfunction "AP_MIPIDSI_DNCLK_PA16") (pintype "passive"))
    )
    (net (code "131") (name "XMIPIDSI1_DP0") (class "Default")
      (node (ref "U1003") (pin "PB17") (pinfunction "AP_MIPIDSI_DP0_PB17") (pintype "passive"))
    )
    (net (code "132") (name "XMIPIDSI1_DP1") (class "Default")
      (node (ref "U1003") (pin "PB18") (pinfunction "AP_MIPIDSI_DP1_PB18") (pintype "passive"))
    )
    (net (code "133") (name "XMIPIDSI1_DP2") (class "Default")
      (node (ref "U1003") (pin "PB19") (pinfunction "AP_MIPIDSI_DP2_PB19") (pintype "passive"))
    )
    (net (code "134") (name "XMIPIDSI1_DP3") (class "Default")
      (node (ref "U1003") (pin "PB20") (pinfunction "AP_MIPIDSI_DP3_PB20") (pintype "passive"))
    )
    (net (code "135") (name "XMIPIDSI1_DPCLK") (class "Default")
      (node (ref "U1003") (pin "PB16") (pinfunction "AP_MIPIDSI_DPCLK_PB16") (pintype "passive"))
    )
    (net (code "136") (name "XPWM0_OUT") (class "Default")
      (node (ref "U1003") (pin "PAK7") (pinfunction "AP_GPC14_PWM2_PAK7") (pintype "passive"))
    )
    (net (code "137") (name "XPWR_KEY") (class "Default")
      (node (ref "U1003") (pin "PAF1") (pinfunction "AP_PWRKEY_(Low_active)_PAF1") (pintype "passive"))
    )
    (net (code "138") (name "XRESET") (class "Default")
      (node (ref "U1003") (pin "PAG1") (pinfunction "AP_NRESET_PAG1") (pintype "passive"))
    )
    (net (code "139") (name "XRTC_INT") (class "Default")
      (node (ref "U1003") (pin "PAE2") (pinfunction "AP_AGP2_RTC_INT_N_PAE2") (pintype "passive"))
    )
    (net (code "140") (name "XRTC_SCL") (class "Default")
      (node (ref "U1003") (pin "PAL20") (pinfunction "AP_GPE3_PAL20") (pintype "passive"))
    )
    (net (code "141") (name "XRTC_SDA") (class "Default")
      (node (ref "U1003") (pin "PAL25") (pinfunction "AP_GPD31_PAL25") (pintype "passive"))
    )
    (net (code "142") (name "XSD0_CDN") (class "Default")
      (node (ref "U1003") (pin "PAL37") (pinfunction "AP_GPB16_PAL37") (pintype "passive"))
    )
    (net (code "143") (name "XSD0_CLK") (class "Default")
      (node (ref "U1003") (pin "PAK30") (pinfunction "AP_SD0_CLK_PAK30") (pintype "passive"))
    )
    (net (code "144") (name "XSD0_CMD") (class "Default")
      (node (ref "U1003") (pin "PAK28") (pinfunction "AP_SD0_CMD_PAK28") (pintype "passive"))
    )
    (net (code "145") (name "XSD0_D0") (class "Default")
      (node (ref "U1003") (pin "PAL30") (pinfunction "AP_SD0_D0_PAL30") (pintype "passive"))
    )
    (net (code "146") (name "XSD0_D1") (class "Default")
      (node (ref "U1003") (pin "PAK29") (pinfunction "AP_SD0_D1_PAK29") (pintype "passive"))
    )
    (net (code "147") (name "XSD0_D2") (class "Default")
      (node (ref "U1003") (pin "PAL29") (pinfunction "AP_SD0_D2_PAL29") (pintype "passive"))
    )
    (net (code "148") (name "XSD0_D3") (class "Default")
      (node (ref "U1003") (pin "PAL28") (pinfunction "AP_SD0_D3_PAL28") (pintype "passive"))
    )
    (net (code "149") (name "XSPI0_CLK") (class "Default")
      (node (ref "U1003") (pin "PAK4") (pinfunction "AP_GPC9_SPI2_CLK_PAK4") (pintype "passive"))
    )
    (net (code "150") (name "XSPI0_CS") (class "Default")
      (node (ref "U1003") (pin "PAL4") (pinfunction "AP_GPC10_SPI2_CS_PAL4") (pintype "passive"))
    )
    (net (code "151") (name "XSPI0_MISO") (class "Default")
      (node (ref "U1003") (pin "PAK3") (pinfunction "AP_GPC11_SPI2_MISO_PAK3") (pintype "passive"))
    )
    (net (code "152") (name "XSPI0_MOSI") (class "Default")
      (node (ref "U1003") (pin "PAL3") (pinfunction "AP_GPC12_SPI2_MOSI_PAL3") (pintype "passive"))
    )
    (net (code "153") (name "XTSP1_GPIO1") (class "Default")
      (node (ref "U1003") (pin "PAL35") (pinfunction "AP_GPC27_PAL35") (pintype "passive"))
    )
    (net (code "154") (name "XTSP1_INT") (class "Default")
      (node (ref "U1003") (pin "PAL36") (pinfunction "AP_GPB22_PAL36") (pintype "passive"))
    )
    (net (code "155") (name "XTSP2_GPIO1") (class "Default")
      (node (ref "U1003") (pin "PAK35") (pinfunction "AP_GPC26_PAK35") (pintype "passive"))
    )
    (net (code "156") (name "XTSP2_INT") (class "Default")
      (node (ref "U1003") (pin "PAK36") (pinfunction "AP_GPB8_PAK36") (pintype "passive"))
    )
    (net (code "157") (name "XTSP_RESET") (class "Default")
      (node (ref "U1003") (pin "PAH42") (pinfunction "AP_GPC25_PAH42") (pintype "passive"))
    )
    (net (code "158") (name "XTSP_SCL") (class "Default")
      (node (ref "U1003") (pin "PAK8") (pinfunction "AP_GPD6_SCL_PAK8") (pintype "passive"))
    )
    (net (code "159") (name "XTSP_SDA") (class "Default")
      (node (ref "U1003") (pin "PAL8") (pinfunction "AP_GPC7_SDA_PAL8") (pintype "passive"))
    )
    (net (code "160") (name "XUART0_RX") (class "Default")
      (node (ref "U1003") (pin "PAL23") (pinfunction "AP_UARTRX4_PAL23") (pintype "passive"))
    )
    (net (code "161") (name "XUART0_TX") (class "Default")
      (node (ref "U1003") (pin "PAK23") (pinfunction "AP_UARTTX4_PAK23") (pintype "passive"))
    )
    (net (code "162") (name "XUHOST1_D_N") (class "Default")
      (node (ref "U1003") (pin "PA36") (pinfunction "AP_USBH_DM_PA36") (pintype "passive"))
    )
    (net (code "163") (name "XUHOST1_D_P") (class "Default")
      (node (ref "U1003") (pin "PB36") (pinfunction "AP_USBH_DP_PB36") (pintype "passive"))
    )
    (net (code "164") (name "XUHOST_VBUSCTRL") (class "Default")
      (node (ref "U1003") (pin "PB41") (pinfunction "AP_GPA16_PB41") (pintype "passive"))
    )
    (net (code "165") (name "XUSB3_D_N") (class "Default")
      (node (ref "U1003") (pin "PA35") (pinfunction "AP_OTG_DM_PA35") (pintype "passive"))
    )
    (net (code "166") (name "XUSB3_D_P") (class "Default")
      (node (ref "U1003") (pin "PB35") (pinfunction "AP_OTG_DP_PB35") (pintype "passive"))
    )
    (net (code "167") (name "XUSB3_ID") (class "Default")
      (node (ref "U1003") (pin "PB37") (pinfunction "AP_OTG_ID_PB37") (pintype "passive"))
    )
    (net (code "168") (name "XUSB3_VBUS") (class "Default")
      (node (ref "U1003") (pin "PD42") (pinfunction "VCC5P0_OTGVBUS1_PD42") (pintype "passive"))
      (node (ref "U1003") (pin "PD43") (pinfunction "VCC5P0_OTGVBUS2_PD43") (pintype "passive"))
    )
    (net (code "169") (name "XUSB3_VBUSCTRL") (class "Default")
      (node (ref "U1003") (pin "PA41") (pinfunction "AP_GPA15_PA41") (pintype "passive"))
    )
    (net (code "170") (name "ZB_JTCK") (class "Default")
      (node (ref "U1003") (pin "PAK13") (pinfunction "ZB_JTCK_PAK13") (pintype "passive"))
    )
    (net (code "171") (name "ZB_JTDI") (class "Default")
      (node (ref "U1003") (pin "PAL12") (pinfunction "ZB_JTDI_PAL12") (pintype "passive"))
    )
    (net (code "172") (name "ZB_JTDO") (class "Default")
      (node (ref "U1003") (pin "PAL13") (pinfunction "ZB_JTDO_PAL13") (pintype "passive"))
    )
    (net (code "173") (name "ZB_JTMS") (class "Default")
      (node (ref "U1003") (pin "PAK12") (pinfunction "ZB_JTMS_PAK12") (pintype "passive"))
    )
    (net (code "174") (name "ZB_PA4") (class "Default")
      (node (ref "U1003") (pin "PAK15") (pinfunction "ZB_PA4_PAK15") (pintype "passive"))
    )
    (net (code "175") (name "ZB_PA5") (class "Default")
      (node (ref "U1003") (pin "PAL15") (pinfunction "ZB_PA5_PAL15") (pintype "passive"))
    )
    (net (code "176") (name "ZB_PC0") (class "Default")
      (node (ref "U1003") (pin "PAK14") (pinfunction "ZB_PC0_PAK14") (pintype "passive"))
    )
    (net (code "177") (name "ZB_RSTN") (class "Default")
      (node (ref "U1003") (pin "PAL14") (pinfunction "ZB_RSTn_PAL14") (pintype "passive"))
    )
    (net (code "178") (name "unconnected-(U1003-AP_NBATTF-PadPAK19)") (class "Default")
      (node (ref "U1003") (pin "PAK19") (pinfunction "AP_NBATTF_PAK19") (pintype "passive+no_connect"))
    )
    (net (code "179") (name "unconnected-(U1003-AP_SPI0_CLK-PadPAK6)") (class "Default")
      (node (ref "U1003") (pin "PAK6") (pinfunction "AP_SPI0_CLK_PAK6") (pintype "passive"))
    )
    (net (code "180") (name "unconnected-(U1003-AP_SPI0_CS-PadPAL6)") (class "Default")
      (node (ref "U1003") (pin "PAL6") (pinfunction "AP_SPI0_CS_PAL6") (pintype "passive"))
    )
    (net (code "181") (name "unconnected-(U1003-AP_SPI0_MOSI-PadPAL5)") (class "Default")
      (node (ref "U1003") (pin "PAL5") (pinfunction "AP_SPI0_MOSI_PAL5") (pintype "passive"))
    )
    (net (code "182") (name "unconnected-(U1003-AP_VDDPWRON-PadPAL19)") (class "Default")
      (node (ref "U1003") (pin "PAL19") (pinfunction "AP_VDDPWRON_PAL19") (pintype "passive+no_connect"))
    )
    (net (code "183") (name "unconnected-(U1003-VCC1P2_LDO10_1-PadPP42)") (class "Default")
      (node (ref "U1003") (pin "PP42") (pinfunction "VCC1P2_LDO10_1_PP42") (pintype "passive+no_connect"))
    )
    (net (code "184") (name "unconnected-(U1003-VCC1P2_LDO10_2-PadPR42)") (class "Default")
      (node (ref "U1003") (pin "PR42") (pinfunction "VCC1P2_LDO10_2_PR42") (pintype "passive+no_connect"))
    )
    (net (code "185") (name "unconnected-(U1003-VCC1P2_LDO10_3-PadPR43)") (class "Default")
      (node (ref "U1003") (pin "PR43") (pinfunction "VCC1P2_LDO10_3_PR43") (pintype "passive+no_connect"))
    )
    (net (code "186") (name "unconnected-(U1003-VCC1P8_LDO4_1-PadPT1)") (class "Default")
      (node (ref "U1003") (pin "PT1") (pinfunction "VCC1P8_LDO4_1_PT1") (pintype "passive+no_connect"))
    )
    (net (code "187") (name "unconnected-(U1003-VCC1P8_LDO4_3-PadPV1)") (class "Default")
      (node (ref "U1003") (pin "PV1") (pinfunction "VCC1P8_LDO4_3_PV1") (pintype "passive+no_connect"))
    )
    (net (code "188") (name "unconnected-(U1003-VCC2P8_LDO7_1-PadPE42)") (class "Default")
      (node (ref "U1003") (pin "PE42") (pinfunction "VCC2P8_LDO7_1_PE42") (pintype "passive+no_connect"))
    )
    (net (code "189") (name "unconnected-(U1003-VCC2P8_LDO7_2-PadPE43)") (class "Default")
      (node (ref "U1003") (pin "PE43") (pinfunction "VCC2P8_LDO7_2_PE43") (pintype "passive+no_connect"))
    )
    (net (code "190") (name "unconnected-(U1003-VCC2P8_LDO7_3-PadPF42)") (class "Default")
      (node (ref "U1003") (pin "PF42") (pinfunction "VCC2P8_LDO7_3_PF42") (pintype "passive+no_connect"))
    )
    (net (code "191") (name "unconnected-(U1003-VCC3V3_LDO8_1-PadPAD42)") (class "Default")
      (node (ref "U1003") (pin "PAD42") (pinfunction "VCC3V3_LDO8_1_PAD42") (pintype "passive+no_connect"))
    )
    (net (code "192") (name "unconnected-(U1003-VCC3V3_LDO8_2-PadPAD43)") (class "Default")
      (node (ref "U1003") (pin "PAD43") (pinfunction "VCC3V3_LDO8_2_PAD43") (pintype "passive+no_connect"))
    )
    (net (code "193") (name "unconnected-(U1003-VCC3V3_LDO8_3-PadPAE43)") (class "Default")
      (node (ref "U1003") (pin "PAE43") (pinfunction "VCC3V3_LDO8_3_PAE43") (pintype "passive+no_connect"))
    )
    (net (code "194") (name "unconnected-(U1003-VCC_1P8_LDO4_2-PadPU1)") (class "Default")
      (node (ref "U1003") (pin "PU1") (pinfunction "VCC_1P8_LDO4_2_PU1") (pintype "passive+no_connect"))
    )
    (net (code "195") (name "unconnected-(U1003-VCC_LDO1_1-PadPM42)") (class "Default")
      (node (ref "U1003") (pin "PM42") (pinfunction "VCC_LDO1_1_PM42") (pintype "passive+no_connect"))
    )
    (net (code "196") (name "unconnected-(U1003-VCC_LDO1_2-PadPM43)") (class "Default")
      (node (ref "U1003") (pin "PM43") (pinfunction "VCC_LDO1_2_PM43") (pintype "passive+no_connect"))
    )
    (net (code "197") (name "unconnected-(U1003-VCC_LDO1_3-PadPN42)") (class "Default")
      (node (ref "U1003") (pin "PN42") (pinfunction "VCC_LDO1_3_PN42") (pintype "passive+no_connect"))
    )
    (net (code "198") (name "unconnected-(U1003-VCC_LDO2_1-PadPJ43)") (class "Default")
      (node (ref "U1003") (pin "PJ43") (pinfunction "VCC_LDO2_1_PJ43") (pintype "passive+no_connect"))
    )
    (net (code "199") (name "unconnected-(U1003-VCC_LDO2_2-PadPK42)") (class "Default")
      (node (ref "U1003") (pin "PK42") (pinfunction "VCC_LDO2_2_PK42") (pintype "passive+no_connect"))
    )
    (net (code "200") (name "unconnected-(U1003-VCC_LDO2_3-PadPK43)") (class "Default")
      (node (ref "U1003") (pin "PK43") (pinfunction "VCC_LDO2_3_PK43") (pintype "passive+no_connect"))
    )
    (net (code "201") (name "unconnected-(U1003-VCC_LDO5_1-PadPH42)") (class "Default")
      (node (ref "U1003") (pin "PH42") (pinfunction "VCC_LDO5_1_PH42") (pintype "passive+no_connect"))
    )
    (net (code "202") (name "unconnected-(U1003-VCC_LDO5_2-PadPH43)") (class "Default")
      (node (ref "U1003") (pin "PH43") (pinfunction "VCC_LDO5_2_PH43") (pintype "passive+no_connect"))
    )
    (net (code "203") (name "unconnected-(U1003-VCC_LDO5_3-PadPJ42)") (class "Default")
      (node (ref "U1003") (pin "PJ42") (pinfunction "VCC_LDO5_3_PJ42") (pintype "passive+no_connect"))
    )
    (net (code "204") (name "unconnected-(U1003-VCC_LDO9_1-PadPT42)") (class "Default")
      (node (ref "U1003") (pin "PT42") (pinfunction "VCC_LDO9_1_PT42") (pintype "passive+no_connect"))
    )
    (net (code "205") (name "unconnected-(U1003-VCC_LDO9_2-PadPU42)") (class "Default")
      (node (ref "U1003") (pin "PU42") (pinfunction "VCC_LDO9_2_PU42") (pintype "passive+no_connect"))
    )
    (net (code "206") (name "unconnected-(U1003-VCC_LDO9_3-PadPU43)") (class "Default")
      (node (ref "U1003") (pin "PU43") (pinfunction "VCC_LDO9_3_PU43") (pintype "passive+no_connect"))
    )
  )
)
